# String_Thing_Pen_1_0.net
KiCad netlist of a schematic drawn in EAGLE
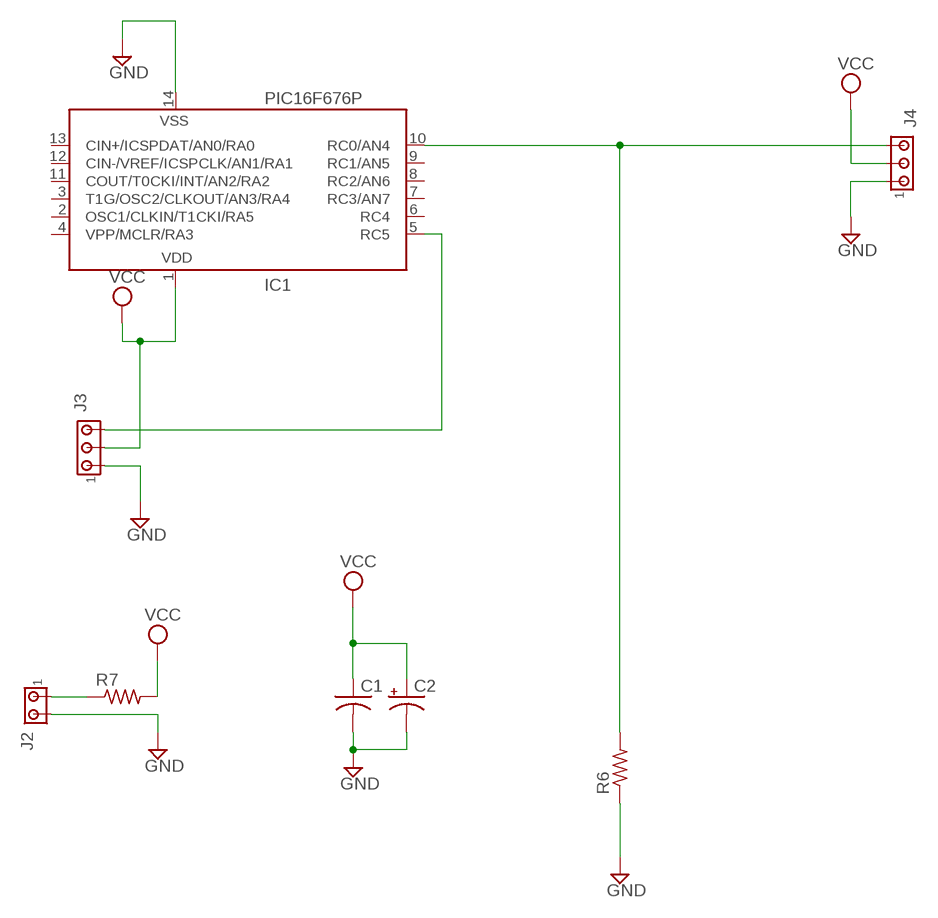
[diagram p0: schematic, sheet 1]

(export (version "E")
  (design (tool "Eeschema 10.0.6"))
  (components
    (comp (ref "C1")
      (value "C-US025-025X050")
      (footprint "eagle-import:C025-025X050")
      (libsource (lib "eagle-import") (part "C-US025-025X050"))
    )
    (comp (ref "C2")
      (value "CPOL-USE2.5-5")
      (footprint "eagle-import:E2,5-5")
      (libsource (lib "eagle-import") (part "CPOL-USE2.5-5"))
    )
    (comp (ref "IC1")
      (value "PIC16F676P")
      (footprint "eagle-import:DIL14")
      (fields (field (name "MF") "MICROCHIP") (field (name "MPN") "PIC16F676-I/P"))
      (libsource (lib "eagle-import") (part "PIC16F676P"))
    )
    (comp (ref "J2")
      (value "MTA02-100")
      (footprint "eagle-import:10X02MTA")
      (libsource (lib "eagle-import") (part "MTA02-100"))
    )
    (comp (ref "J3")
      (value "MTA03-100")
      (footprint "eagle-import:10X03MTA")
      (libsource (lib "eagle-import") (part "MTA03-100"))
    )
    (comp (ref "J4")
      (value "MTA03-100")
      (footprint "eagle-import:10X03MTA")
      (libsource (lib "eagle-import") (part "MTA03-100"))
    )
    (comp (ref "R6")
      (value "R-US_0207/10")
      (footprint "eagle-import:0207_10")
      (libsource (lib "eagle-import") (part "R-US_0207/10"))
    )
    (comp (ref "R7")
      (value "R-US_0207/10")
      (footprint "eagle-import:0207_10")
      (libsource (lib "eagle-import") (part "R-US_0207/10"))
    )
  )
  (nets
    (net (code "1") (name "GND") (class "Default")
      (node (ref "C1") (pin "2") (pinfunction "2_2") (pintype "passive"))
      (node (ref "C2") (pin "-") (pinfunction "-_-") (pintype "passive"))
      (node (ref "IC1") (pin "14") (pinfunction "VSS_14") (pintype "power_in"))
      (node (ref "J2") (pin "2") (pinfunction "2_2") (pintype "passive"))
      (node (ref "J3") (pin "1") (pinfunction "1_1") (pintype "passive"))
      (node (ref "J4") (pin "1") (pinfunction "1_1") (pintype "passive"))
      (node (ref "R6") (pin "1") (pinfunction "1_1") (pintype "passive"))
    )
    (net (code "2") (name "Net-(IC1-RC0{slash}AN4)") (class "Default")
      (node (ref "IC1") (pin "10") (pinfunction "RC0/AN4_10") (pintype "bidirectional"))
      (node (ref "J4") (pin "3") (pinfunction "3_3") (pintype "passive"))
      (node (ref "R6") (pin "2") (pinfunction "2_2") (pintype "passive"))
    )
    (net (code "3") (name "Net-(IC1-RC5)") (class "Default")
      (node (ref "IC1") (pin "5") (pinfunction "RC5_5") (pintype "bidirectional"))
      (node (ref "J3") (pin "3") (pinfunction "3_3") (pintype "passive"))
    )
    (net (code "4") (name "Net-(J2-Pad1)") (class "Default")
      (node (ref "J2") (pin "1") (pinfunction "1_1") (pintype "passive"))
      (node (ref "R7") (pin "1") (pinfunction "1_1") (pintype "passive"))
    )
    (net (code "5") (name "VCC") (class "Default")
      (node (ref "C1") (pin "1") (pinfunction "1_1") (pintype "passive"))
      (node (ref "C2") (pin "+") (pinfunction "+_+") (pintype "passive"))
      (node (ref "IC1") (pin "1") (pinfunction "VDD_1") (pintype "power_in"))
      (node (ref "J3") (pin "2") (pinfunction "2_2") (pintype "passive"))
      (node (ref "J4") (pin "2") (pinfunction "2_2") (pintype "passive"))
      (node (ref "R7") (pin "2") (pinfunction "2_2") (pintype "passive"))
    )
    (net (code "6") (name "unconnected-(IC1-CIN+{slash}ICSPDAT{slash}AN0{slash}RA0-Pad13)") (class "Default")
      (node (ref "IC1") (pin "13") (pinfunction "CIN+/ICSPDAT/AN0/RA0_13") (pintype "bidirectional"))
    )
    (net (code "7") (name "unconnected-(IC1-CIN-{slash}VREF{slash}ICSPCLK{slash}AN1{slash}RA1-Pad12)") (class "Default")
      (node (ref "IC1") (pin "12") (pinfunction "CIN-/VREF/ICSPCLK/AN1/RA1_12") (pintype "bidirectional"))
    )
    (net (code "8") (name "unconnected-(IC1-COUT{slash}T0CKI{slash}INT{slash}AN2{slash}RA2-Pad11)") (class "Default")
      (node (ref "IC1") (pin "11") (pinfunction "COUT/T0CKI/INT/AN2/RA2_11") (pintype "bidirectional"))
    )
    (net (code "9") (name "unconnected-(IC1-OSC1{slash}CLKIN{slash}T1CKI{slash}RA5-Pad2)") (class "Default")
      (node (ref "IC1") (pin "2") (pinfunction "OSC1/CLKIN/T1CKI/RA5_2") (pintype "bidirectional"))
    )
    (net (code "10") (name "unconnected-(IC1-RC1{slash}AN5-Pad9)") (class "Default")
      (node (ref "IC1") (pin "9") (pinfunction "RC1/AN5_9") (pintype "bidirectional"))
    )
    (net (code "11") (name "unconnected-(IC1-RC2{slash}AN6-Pad8)") (class "Default")
      (node (ref "IC1") (pin "8") (pinfunction "RC2/AN6_8") (pintype "bidirectional"))
    )
    (net (code "12") (name "unconnected-(IC1-RC3{slash}AN7-Pad7)") (class "Default")
      (node (ref "IC1") (pin "7") (pinfunction "RC3/AN7_7") (pintype "bidirectional"))
    )
    (net (code "13") (name "unconnected-(IC1-RC4-Pad6)") (class "Default")
      (node (ref "IC1") (pin "6") (pinfunction "RC4_6") (pintype "bidirectional"))
    )
    (net (code "14") (name "unconnected-(IC1-T1G{slash}OSC2{slash}CLKOUT{slash}AN3{slash}RA4-Pad3)") (class "Default")
      (node (ref "IC1") (pin "3") (pinfunction "T1G/OSC2/CLKOUT/AN3/RA4_3") (pintype "bidirectional"))
    )
    (net (code "15") (name "unconnected-(IC1-VPP{slash}MCLR{slash}RA3-Pad4)") (class "Default")
      (node (ref "IC1") (pin "4") (pinfunction "VPP/MCLR/RA3_4") (pintype "input"))
    )
  )
)
